# TK103_Multiplexer.net
KiCad netlist of a schematic drawn in Altium Designer
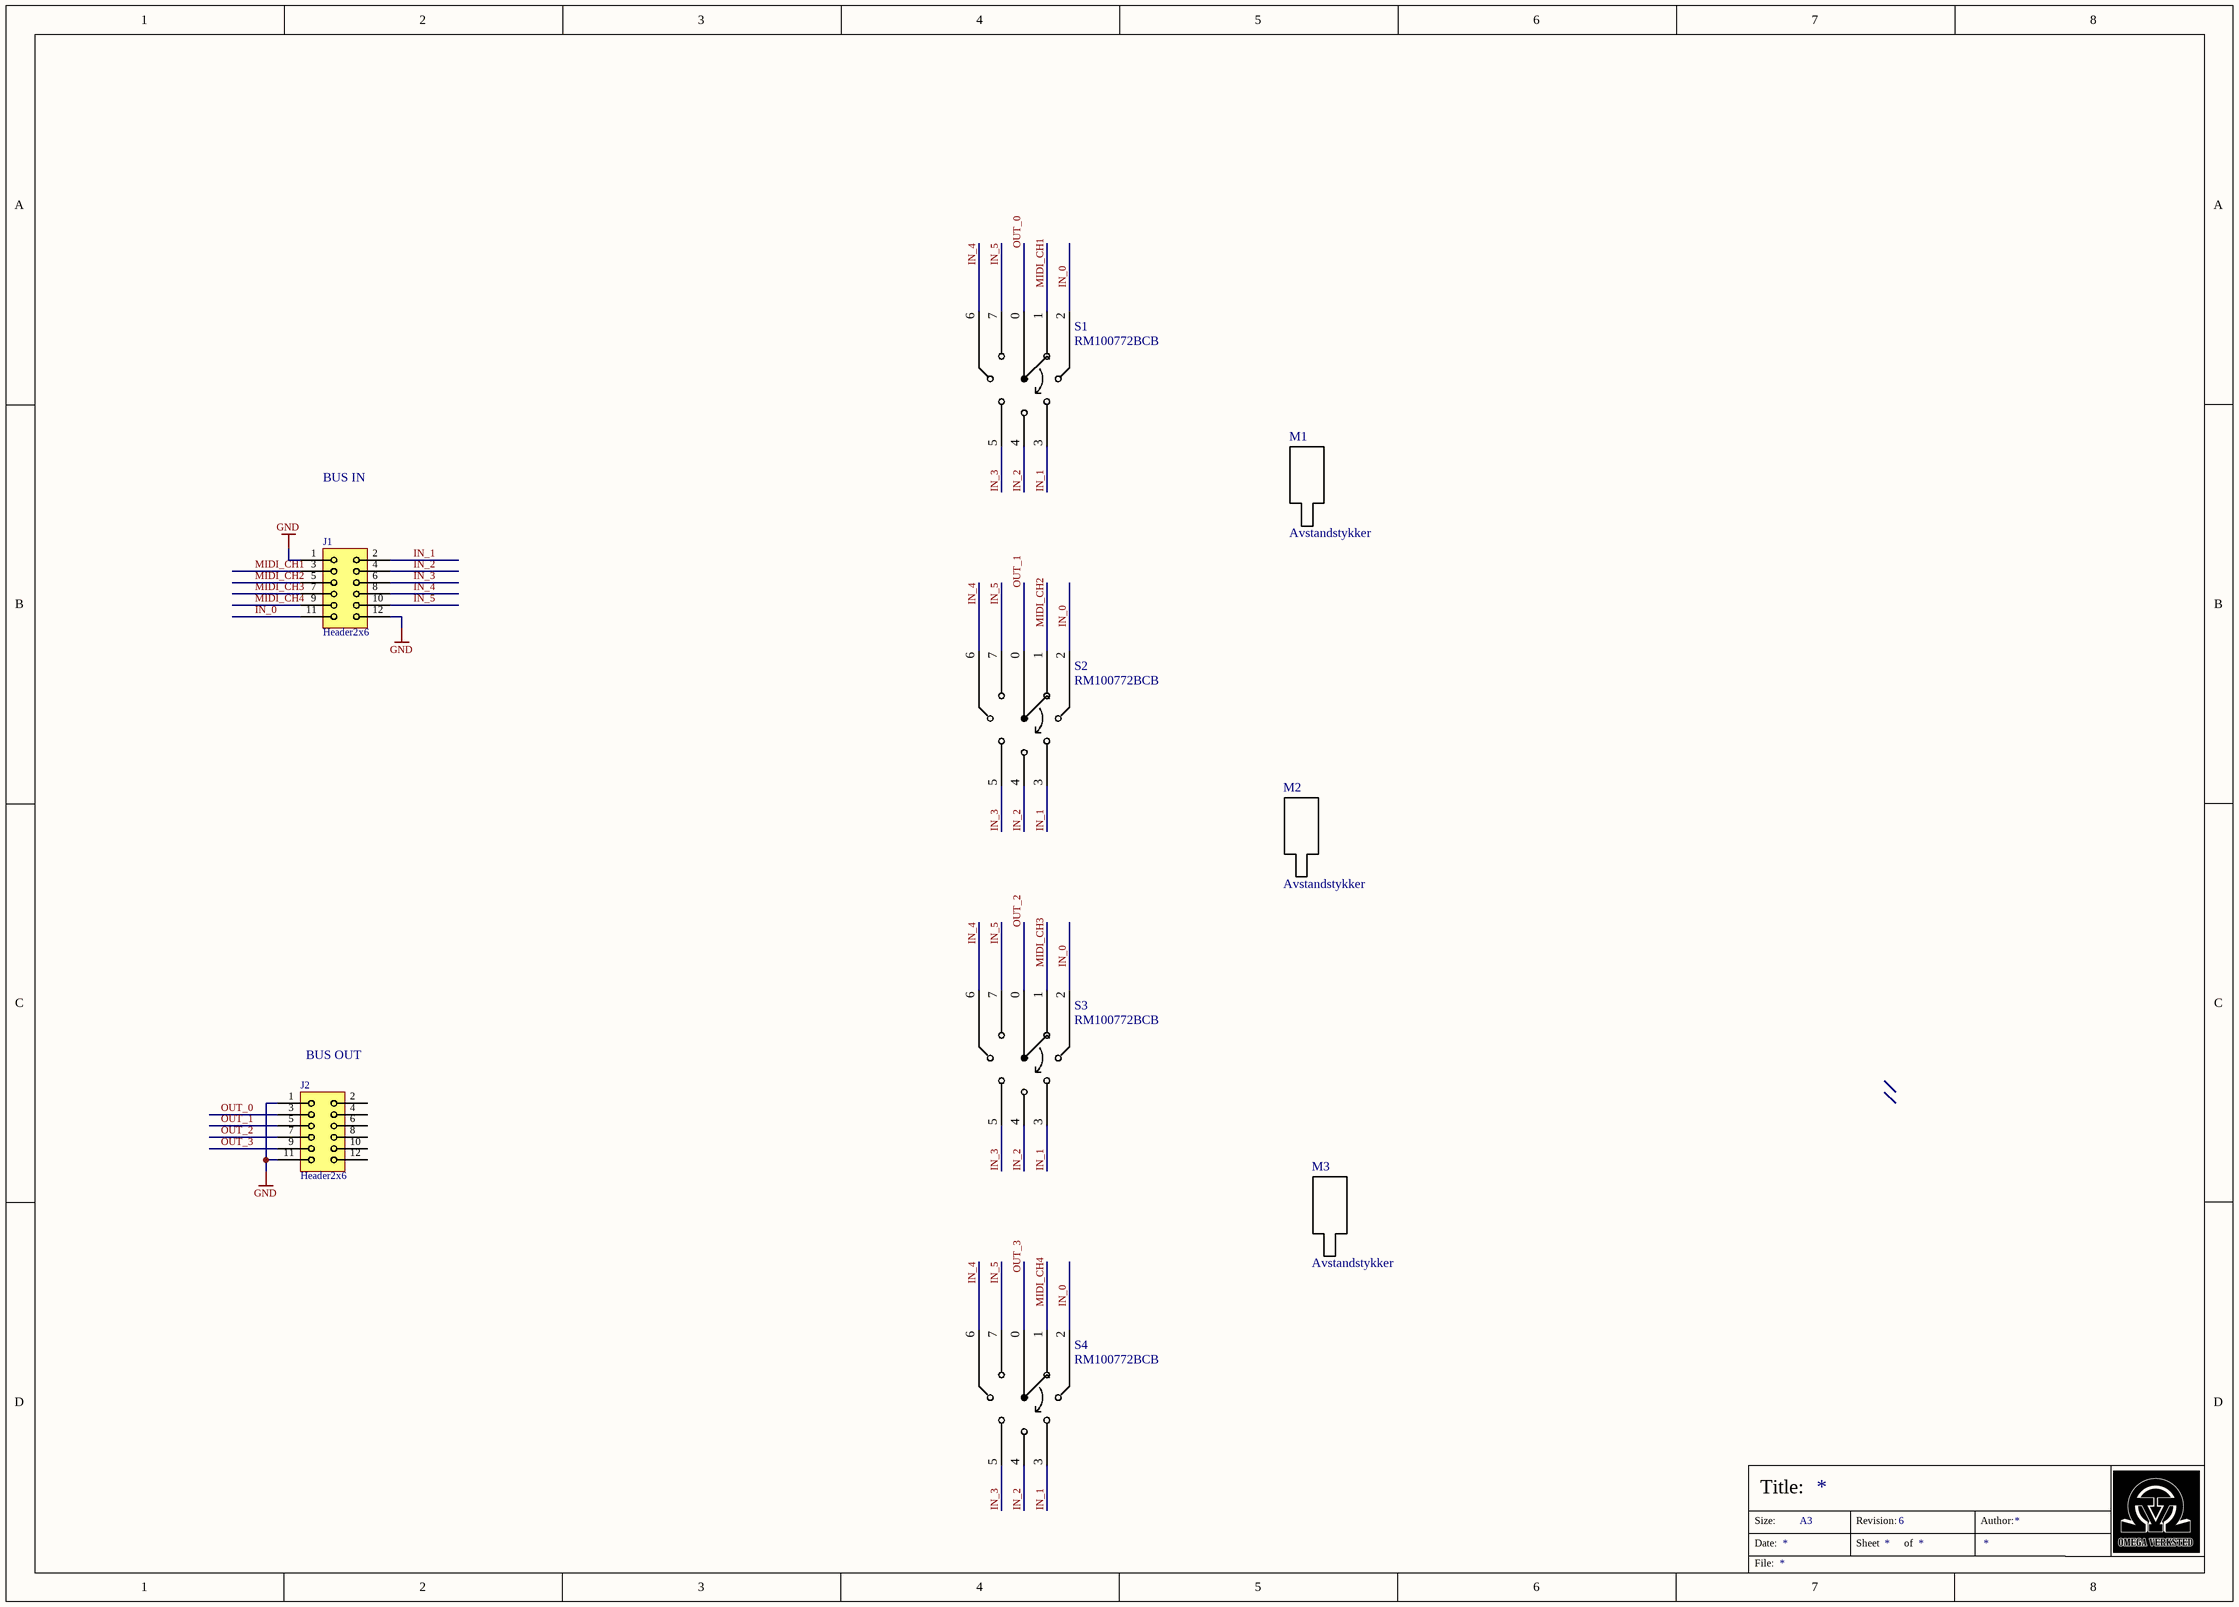
[diagram p0: TK103_Multiplexer.SchDoc]

(export (version "E")
  (design (tool "Eeschema 10.0.6"))
  (components
    (comp (ref "J1")
      (value "Header2x6")
      (footprint "HDRV12W64P254_2X6_Shrouded")
      (libsource (lib "OVLib_64") (part "Header2x6"))
    )
    (comp (ref "J2")
      (value "Header2x6")
      (footprint "HDRV12W64P254_2X6_Shrouded")
      (libsource (lib "OVLib_64") (part "Header2x6"))
    )
    (comp (ref "M1")
      (value "Avstandstykker")
      (footprint "M3_Spacer_Inverted")
      (description "M3 Hex Threaded Nylon Spacer")
      (libsource (lib "OVLib_64") (part "Spacer"))
    )
    (comp (ref "M2")
      (value "Avstandstykker")
      (footprint "M3_Spacer_Inverted")
      (description "M3 Hex Threaded Nylon Spacer")
      (libsource (lib "OVLib_64") (part "Spacer"))
    )
    (comp (ref "M3")
      (value "Avstandstykker")
      (footprint "M3_Spacer_Inverted")
      (description "M3 Hex Threaded Nylon Spacer")
      (libsource (lib "OVLib_64") (part "Spacer"))
    )
    (comp (ref "S1")
      (value "RM100772BCB")
      (footprint "RM100772BCB")
      (description "SWITCH ROTARY 8POS 500MA 24V")
      (libsource (lib "OVLib_64") (part "RotarySwith_8pole"))
    )
    (comp (ref "S2")
      (value "RM100772BCB")
      (footprint "RM100772BCB")
      (description "SWITCH ROTARY 8POS 500MA 24V")
      (libsource (lib "OVLib_64") (part "RotarySwith_8pole"))
    )
    (comp (ref "S3")
      (value "RM100772BCB")
      (footprint "RM100772BCB")
      (description "SWITCH ROTARY 8POS 500MA 24V")
      (libsource (lib "OVLib_64") (part "RotarySwith_8pole"))
    )
    (comp (ref "S4")
      (value "RM100772BCB")
      (footprint "RM100772BCB")
      (description "SWITCH ROTARY 8POS 500MA 24V")
      (libsource (lib "OVLib_64") (part "RotarySwith_8pole"))
    )
  )
  (nets
    (net (code "1") (name "/IN_0") (class "Default")
      (node (ref "J1") (pin "11") (pinfunction "11_11") (pintype "passive"))
      (node (ref "S1") (pin "2") (pinfunction "2_2") (pintype "passive"))
      (node (ref "S2") (pin "2") (pinfunction "2_2") (pintype "passive"))
      (node (ref "S3") (pin "2") (pinfunction "2_2") (pintype "passive"))
      (node (ref "S4") (pin "2") (pinfunction "2_2") (pintype "passive"))
    )
    (net (code "2") (name "/IN_1") (class "Default")
      (node (ref "J1") (pin "2") (pinfunction "2_2") (pintype "passive"))
      (node (ref "S1") (pin "3") (pinfunction "3_3") (pintype "passive"))
      (node (ref "S2") (pin "3") (pinfunction "3_3") (pintype "passive"))
      (node (ref "S3") (pin "3") (pinfunction "3_3") (pintype "passive"))
      (node (ref "S4") (pin "3") (pinfunction "3_3") (pintype "passive"))
    )
    (net (code "3") (name "/IN_2") (class "Default")
      (node (ref "J1") (pin "4") (pinfunction "4_4") (pintype "passive"))
      (node (ref "S1") (pin "4") (pinfunction "4_4") (pintype "passive"))
      (node (ref "S2") (pin "4") (pinfunction "4_4") (pintype "passive"))
      (node (ref "S3") (pin "4") (pinfunction "4_4") (pintype "passive"))
      (node (ref "S4") (pin "4") (pinfunction "4_4") (pintype "passive"))
    )
    (net (code "4") (name "/IN_3") (class "Default")
      (node (ref "J1") (pin "6") (pinfunction "6_6") (pintype "passive"))
      (node (ref "S1") (pin "5") (pinfunction "5_5") (pintype "passive"))
      (node (ref "S2") (pin "5") (pinfunction "5_5") (pintype "passive"))
      (node (ref "S3") (pin "5") (pinfunction "5_5") (pintype "passive"))
      (node (ref "S4") (pin "5") (pinfunction "5_5") (pintype "passive"))
    )
    (net (code "5") (name "/IN_4") (class "Default")
      (node (ref "J1") (pin "8") (pinfunction "8_8") (pintype "passive"))
      (node (ref "S1") (pin "6") (pinfunction "6_6") (pintype "passive"))
      (node (ref "S2") (pin "6") (pinfunction "6_6") (pintype "passive"))
      (node (ref "S3") (pin "6") (pinfunction "6_6") (pintype "passive"))
      (node (ref "S4") (pin "6") (pinfunction "6_6") (pintype "passive"))
    )
    (net (code "6") (name "/IN_5") (class "Default")
      (node (ref "J1") (pin "10") (pinfunction "10_10") (pintype "passive"))
      (node (ref "S1") (pin "7") (pinfunction "7_7") (pintype "passive"))
      (node (ref "S2") (pin "7") (pinfunction "7_7") (pintype "passive"))
      (node (ref "S3") (pin "7") (pinfunction "7_7") (pintype "passive"))
      (node (ref "S4") (pin "7") (pinfunction "7_7") (pintype "passive"))
    )
    (net (code "7") (name "/MIDI_CH1") (class "Default")
      (node (ref "J1") (pin "3") (pinfunction "3_3") (pintype "passive"))
      (node (ref "S1") (pin "1") (pinfunction "1_1") (pintype "passive"))
    )
    (net (code "8") (name "/MIDI_CH2") (class "Default")
      (node (ref "J1") (pin "5") (pinfunction "5_5") (pintype "passive"))
      (node (ref "S2") (pin "1") (pinfunction "1_1") (pintype "passive"))
    )
    (net (code "9") (name "/MIDI_CH3") (class "Default")
      (node (ref "J1") (pin "7") (pinfunction "7_7") (pintype "passive"))
      (node (ref "S3") (pin "1") (pinfunction "1_1") (pintype "passive"))
    )
    (net (code "10") (name "/MIDI_CH4") (class "Default")
      (node (ref "J1") (pin "9") (pinfunction "9_9") (pintype "passive"))
      (node (ref "S4") (pin "1") (pinfunction "1_1") (pintype "passive"))
    )
    (net (code "11") (name "/OUT_0") (class "Default")
      (node (ref "J2") (pin "3") (pinfunction "3_3") (pintype "passive"))
      (node (ref "S1") (pin "0") (pinfunction "0_0") (pintype "passive"))
    )
    (net (code "12") (name "/OUT_1") (class "Default")
      (node (ref "J2") (pin "5") (pinfunction "5_5") (pintype "passive"))
      (node (ref "S2") (pin "0") (pinfunction "0_0") (pintype "passive"))
    )
    (net (code "13") (name "/OUT_2") (class "Default")
      (node (ref "J2") (pin "7") (pinfunction "7_7") (pintype "passive"))
      (node (ref "S3") (pin "0") (pinfunction "0_0") (pintype "passive"))
    )
    (net (code "14") (name "/OUT_3") (class "Default")
      (node (ref "J2") (pin "9") (pinfunction "9_9") (pintype "passive"))
      (node (ref "S4") (pin "0") (pinfunction "0_0") (pintype "passive"))
    )
    (net (code "15") (name "GND") (class "Default")
      (node (ref "J1") (pin "1") (pinfunction "1_1") (pintype "passive"))
      (node (ref "J1") (pin "12") (pinfunction "12_12") (pintype "passive"))
      (node (ref "J2") (pin "1") (pinfunction "1_1") (pintype "passive"))
      (node (ref "J2") (pin "11") (pinfunction "11_11") (pintype "passive"))
    )
    (net (code "16") (name "unconnected-(J2-Pad2)") (class "Default")
      (node (ref "J2") (pin "2") (pinfunction "2_2") (pintype "passive"))
    )
    (net (code "17") (name "unconnected-(J2-Pad4)") (class "Default")
      (node (ref "J2") (pin "4") (pinfunction "4_4") (pintype "passive"))
    )
    (net (code "18") (name "unconnected-(J2-Pad6)") (class "Default")
      (node (ref "J2") (pin "6") (pinfunction "6_6") (pintype "passive"))
    )
    (net (code "19") (name "unconnected-(J2-Pad8)") (class "Default")
      (node (ref "J2") (pin "8") (pinfunction "8_8") (pintype "passive"))
    )
    (net (code "20") (name "unconnected-(J2-Pad10)") (class "Default")
      (node (ref "J2") (pin "10") (pinfunction "10_10") (pintype "passive"))
    )
    (net (code "21") (name "unconnected-(J2-Pad12)") (class "Default")
      (node (ref "J2") (pin "12") (pinfunction "12_12") (pintype "passive"))
    )
  )
)
